# cwKeyer.net
KiCad netlist of a schematic drawn in EAGLE
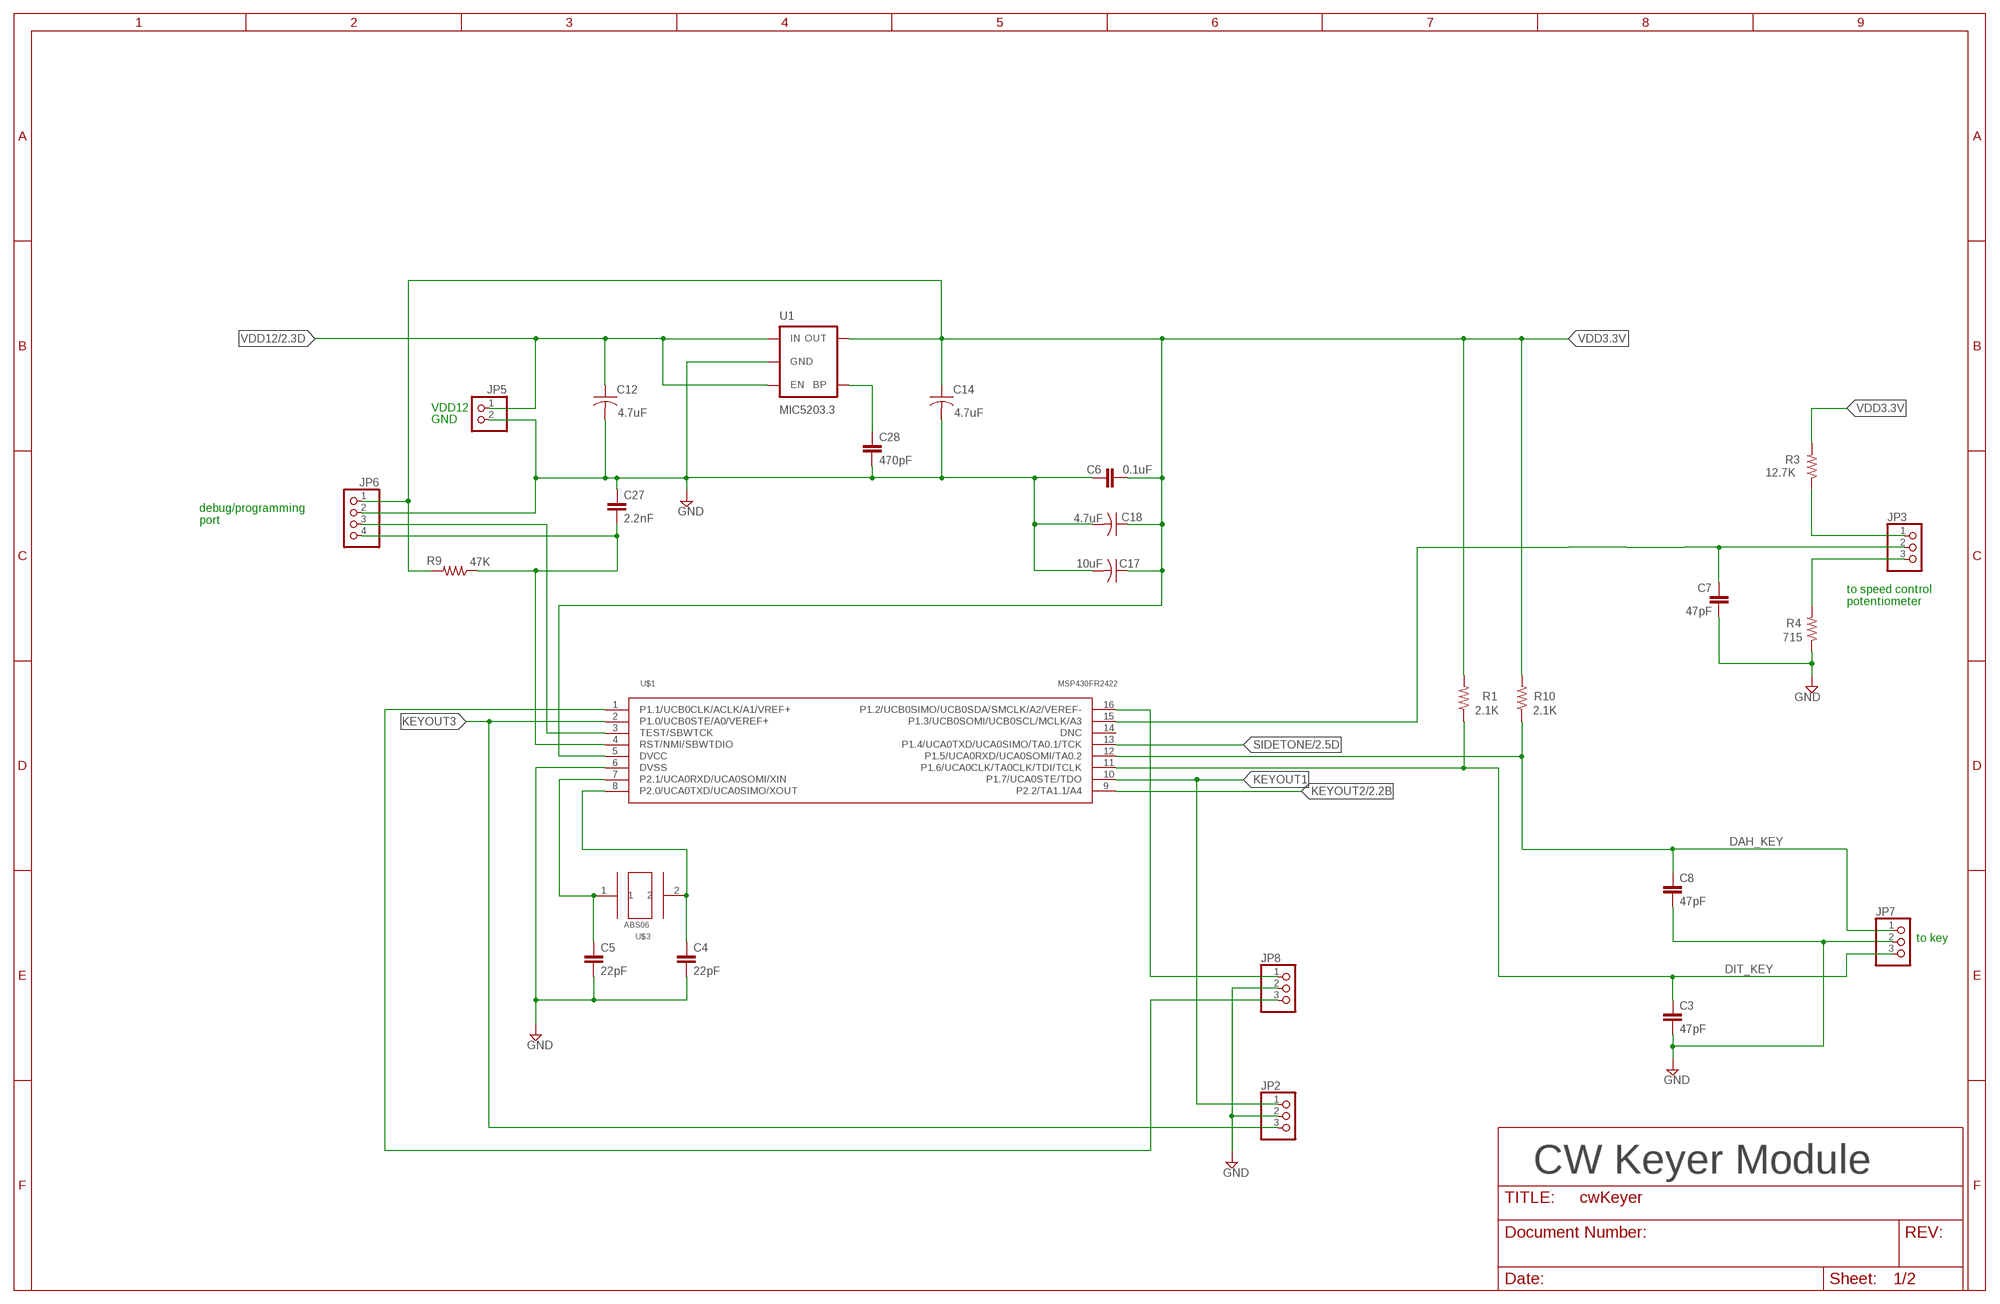
[diagram p0: schematic, sheet 1]
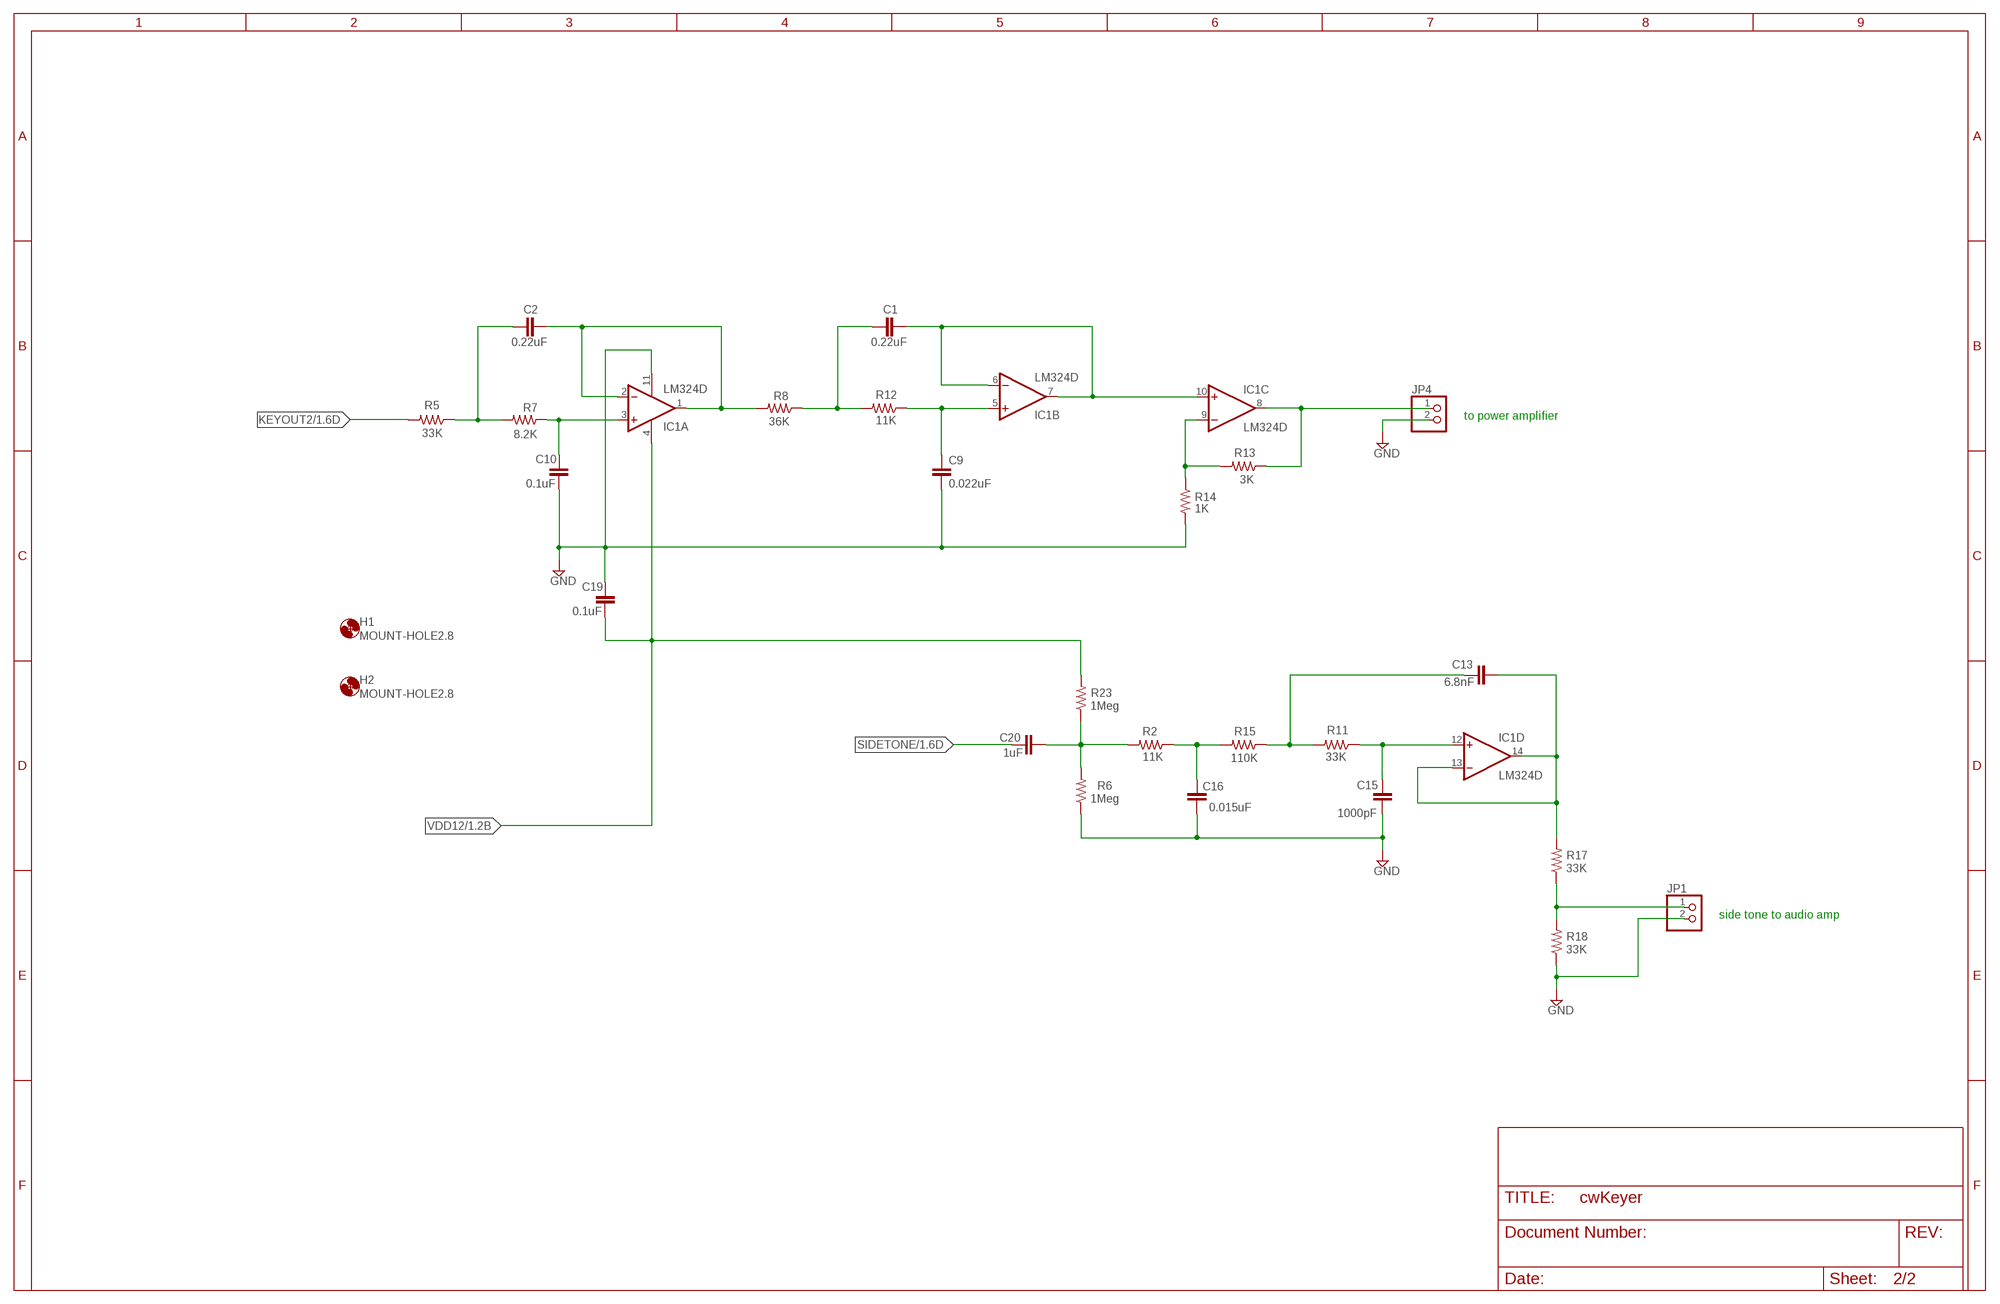
[diagram p1: schematic, sheet 2]

(export (version "E")
  (design (tool "Eeschema 10.0.6"))
  (components
    (comp (ref "C1")
      (value "0.22uF")
      (footprint "eagle-import:0603-CAP")
      (libsource (lib "eagle-import") (part "SparkFun-Passives_CAP0603-CAP"))
    )
    (comp (ref "C2")
      (value "0.22uF")
      (footprint "eagle-import:0603-CAP")
      (libsource (lib "eagle-import") (part "SparkFun-Passives_CAP0603-CAP"))
    )
    (comp (ref "C9")
      (value "0.022uF")
      (footprint "eagle-import:0603-CAP")
      (libsource (lib "eagle-import") (part "SparkFun-Passives_CAP0603-CAP"))
    )
    (comp (ref "C10")
      (value "0.1uF")
      (footprint "eagle-import:0603-CAP")
      (libsource (lib "eagle-import") (part "SparkFun-Passives_CAP0603-CAP"))
    )
    (comp (ref "C13")
      (value "6.8nF")
      (footprint "eagle-import:0603-CAP")
      (libsource (lib "eagle-import") (part "SparkFun-Passives_CAP0603-CAP"))
    )
    (comp (ref "C15")
      (value "1000pF")
      (footprint "eagle-import:0603-CAP")
      (libsource (lib "eagle-import") (part "SparkFun-Passives_CAP0603-CAP"))
    )
    (comp (ref "C16")
      (value "0.015uF")
      (footprint "eagle-import:0603-CAP")
      (libsource (lib "eagle-import") (part "SparkFun-Passives_CAP0603-CAP"))
    )
    (comp (ref "C19")
      (value "0.1uF")
      (footprint "eagle-import:0603-CAP")
      (libsource (lib "eagle-import") (part "SparkFun-Passives_CAP0603-CAP"))
    )
    (comp (ref "C20")
      (value "1uF")
      (footprint "eagle-import:0603-CAP")
      (libsource (lib "eagle-import") (part "SparkFun-Passives_CAP0603-CAP"))
    )
    (comp (ref "H1")
      (value "MOUNT-HOLE2.8")
      (footprint "eagle-import:2,8")
      (libsource (lib "eagle-import") (part "MOUNT-HOLE2.8"))
    )
    (comp (ref "H2")
      (value "MOUNT-HOLE2.8")
      (footprint "eagle-import:2,8")
      (libsource (lib "eagle-import") (part "MOUNT-HOLE2.8"))
    )
    (comp (ref "IC1")
      (value "LM324D")
      (footprint "eagle-import:SO14")
      (fields (field (name "VENDOR") "Mouser") (field (name "VENDOR_PN") "595-LM324DR"))
      (libsource (lib "eagle-import") (part "LM324D"))
    )
    (comp (ref "JP1")
      (value "PINHD-1X2")
      (footprint "eagle-import:1X02")
      (libsource (lib "eagle-import") (part "PINHD-1X2"))
    )
    (comp (ref "JP4")
      (value "PINHD-1X2")
      (footprint "eagle-import:1X02")
      (libsource (lib "eagle-import") (part "PINHD-1X2"))
    )
    (comp (ref "R2")
      (value "11K")
      (footprint "eagle-import:0603-RES")
      (libsource (lib "eagle-import") (part "RESISTOR0603-RES"))
    )
    (comp (ref "R5")
      (value "33K")
      (footprint "eagle-import:0603-RES")
      (libsource (lib "eagle-import") (part "RESISTOR0603-RES"))
    )
    (comp (ref "R6")
      (value "1Meg")
      (footprint "eagle-import:0603-RES")
      (libsource (lib "eagle-import") (part "RESISTOR0603-RES"))
    )
    (comp (ref "R7")
      (value "8.2K")
      (footprint "eagle-import:0603-RES")
      (libsource (lib "eagle-import") (part "RESISTOR0603-RES"))
    )
    (comp (ref "R8")
      (value "36K")
      (footprint "eagle-import:0603-RES")
      (libsource (lib "eagle-import") (part "RESISTOR0603-RES"))
    )
    (comp (ref "R11")
      (value "33K")
      (footprint "eagle-import:0603-RES")
      (libsource (lib "eagle-import") (part "RESISTOR0603-RES"))
    )
    (comp (ref "R12")
      (value "11K")
      (footprint "eagle-import:0603-RES")
      (libsource (lib "eagle-import") (part "RESISTOR0603-RES"))
    )
    (comp (ref "R13")
      (value "3K")
      (footprint "eagle-import:0603-RES")
      (libsource (lib "eagle-import") (part "RESISTOR0603-RES"))
    )
    (comp (ref "R14")
      (value "1K")
      (footprint "eagle-import:0603-RES")
      (libsource (lib "eagle-import") (part "RESISTOR0603-RES"))
    )
    (comp (ref "R15")
      (value "110K")
      (footprint "eagle-import:0603-RES")
      (libsource (lib "eagle-import") (part "RESISTOR0603-RES"))
    )
    (comp (ref "R17")
      (value "33K")
      (footprint "eagle-import:0603-RES")
      (libsource (lib "eagle-import") (part "RESISTOR0603-RES"))
    )
    (comp (ref "R18")
      (value "33K")
      (footprint "eagle-import:0603-RES")
      (libsource (lib "eagle-import") (part "RESISTOR0603-RES"))
    )
    (comp (ref "R23")
      (value "1Meg")
      (footprint "eagle-import:0603-RES")
      (libsource (lib "eagle-import") (part "RESISTOR0603-RES"))
    )
    (comp (ref "C3")
      (value "47pF")
      (footprint "eagle-import:0603-CAP")
      (libsource (lib "eagle-import") (part "SparkFun-Passives_CAP0603-CAP"))
    )
    (comp (ref "C4")
      (value "22pF")
      (footprint "eagle-import:0603-CAP")
      (libsource (lib "eagle-import") (part "CAP0603-CAP"))
    )
    (comp (ref "C5")
      (value "22pF")
      (footprint "eagle-import:0603-CAP")
      (libsource (lib "eagle-import") (part "CAP0603-CAP"))
    )
    (comp (ref "C6")
      (value "0.1uF")
      (footprint "eagle-import:0603-CAP")
      (libsource (lib "eagle-import") (part "SparkFun-Passives_CAP0603-CAP"))
    )
    (comp (ref "C7")
      (value "47pF")
      (footprint "eagle-import:0603-CAP")
      (libsource (lib "eagle-import") (part "SparkFun-Passives_CAP0603-CAP"))
    )
    (comp (ref "C8")
      (value "47pF")
      (footprint "eagle-import:0603-CAP")
      (libsource (lib "eagle-import") (part "SparkFun-Passives_CAP0603-CAP"))
    )
    (comp (ref "C12")
      (value "4.7uF")
      (footprint "eagle-import:C0603")
      (libsource (lib "eagle-import") (part "C-USC0603"))
    )
    (comp (ref "C14")
      (value "4.7uF")
      (footprint "eagle-import:C0603")
      (libsource (lib "eagle-import") (part "C-USC0603"))
    )
    (comp (ref "C17")
      (value "10uF")
      (footprint "eagle-import:C0805")
      (libsource (lib "eagle-import") (part "C-USC0805"))
    )
    (comp (ref "C18")
      (value "4.7uF")
      (footprint "eagle-import:C0603")
      (libsource (lib "eagle-import") (part "C-USC0603"))
    )
    (comp (ref "C27")
      (value "2.2nF")
      (footprint "eagle-import:0603-CAP")
      (libsource (lib "eagle-import") (part "SparkFun-Passives_CAP0603-CAP"))
    )
    (comp (ref "C28")
      (value "470pF")
      (footprint "eagle-import:0603-CAP")
      (libsource (lib "eagle-import") (part "CAP0603-CAP"))
    )
    (comp (ref "JP2")
      (value "PINHD-1X3")
      (footprint "eagle-import:1X03")
      (libsource (lib "eagle-import") (part "PINHD-1X3"))
    )
    (comp (ref "JP3")
      (value "PINHD-1X3")
      (footprint "eagle-import:1X03")
      (libsource (lib "eagle-import") (part "PINHD-1X3"))
    )
    (comp (ref "JP5")
      (value "PINHD-1X2")
      (footprint "eagle-import:1X02")
      (libsource (lib "eagle-import") (part "PINHD-1X2"))
    )
    (comp (ref "JP6")
      (value "PINHD-1X4")
      (footprint "eagle-import:1X04")
      (libsource (lib "eagle-import") (part "PINHD-1X4"))
    )
    (comp (ref "JP7")
      (value "PINHD-1X3")
      (footprint "eagle-import:1X03")
      (libsource (lib "eagle-import") (part "PINHD-1X3"))
    )
    (comp (ref "JP8")
      (value "PINHD-1X3")
      (footprint "eagle-import:1X03")
      (libsource (lib "eagle-import") (part "PINHD-1X3"))
    )
    (comp (ref "R1")
      (value "2.1K")
      (footprint "eagle-import:0603-RES")
      (libsource (lib "eagle-import") (part "RESISTOR0603-RES"))
    )
    (comp (ref "R3")
      (value "12.7K")
      (footprint "eagle-import:0603-RES")
      (libsource (lib "eagle-import") (part "RESISTOR0603-RES"))
    )
    (comp (ref "R4")
      (value "715")
      (footprint "eagle-import:0603-RES")
      (libsource (lib "eagle-import") (part "RESISTOR0603-RES"))
    )
    (comp (ref "R9")
      (value "47K")
      (footprint "eagle-import:0603-RES")
      (libsource (lib "eagle-import") (part "RESISTOR0603-RES"))
    )
    (comp (ref "R10")
      (value "2.1K")
      (footprint "eagle-import:0603-RES")
      (libsource (lib "eagle-import") (part "RESISTOR0603-RES"))
    )
    (comp (ref "U$1")
      (value "MSP430FR2422")
      (footprint "eagle-import:TSSOP16")
      (libsource (lib "eagle-import") (part "MSP430FR2422"))
    )
    (comp (ref "U$3")
      (value "ABS06")
      (footprint "eagle-import:ABS06")
      (libsource (lib "eagle-import") (part "ABS06"))
    )
    (comp (ref "U1")
      (value "MIC5203.3")
      (footprint "eagle-import:SOT23-5")
      (libsource (lib "eagle-import") (part "MIC52053.3V"))
    )
  )
  (nets
    (net (code "1") (name "DAH_KEY") (class "Default")
      (node (ref "C8") (pin "1") (pinfunction "1_1") (pintype "passive"))
      (node (ref "JP7") (pin "1") (pinfunction "1_1") (pintype "passive"))
      (node (ref "R10") (pin "1") (pinfunction "1_1") (pintype "passive"))
      (node (ref "U$1") (pin "12") (pinfunction "P1.5/UCA0RXD/UCA0SOMI/TA0.2_12") (pintype "bidirectional"))
    )
    (net (code "2") (name "DIT_KEY") (class "Default")
      (node (ref "C3") (pin "1") (pinfunction "1_1") (pintype "passive"))
      (node (ref "JP7") (pin "3") (pinfunction "3_3") (pintype "passive"))
      (node (ref "R1") (pin "1") (pinfunction "1_1") (pintype "passive"))
      (node (ref "U$1") (pin "11") (pinfunction "P1.6/UCA0CLK/TA0CLK/TDI/TCLK_11") (pintype "bidirectional"))
    )
    (net (code "3") (name "GND") (class "Default")
      (node (ref "C10") (pin "2") (pinfunction "2_2") (pintype "passive"))
      (node (ref "C12") (pin "2") (pinfunction "2_2") (pintype "passive"))
      (node (ref "C14") (pin "2") (pinfunction "2_2") (pintype "passive"))
      (node (ref "C15") (pin "1") (pinfunction "1_1") (pintype "passive"))
      (node (ref "C16") (pin "1") (pinfunction "1_1") (pintype "passive"))
      (node (ref "C17") (pin "2") (pinfunction "2_2") (pintype "passive"))
      (node (ref "C18") (pin "2") (pinfunction "2_2") (pintype "passive"))
      (node (ref "C19") (pin "1") (pinfunction "1_1") (pintype "passive"))
      (node (ref "C27") (pin "1") (pinfunction "1_1") (pintype "passive"))
      (node (ref "C28") (pin "2") (pinfunction "2_2") (pintype "passive"))
      (node (ref "C3") (pin "2") (pinfunction "2_2") (pintype "passive"))
      (node (ref "C4") (pin "2") (pinfunction "2_2") (pintype "passive"))
      (node (ref "C5") (pin "2") (pinfunction "2_2") (pintype "passive"))
      (node (ref "C6") (pin "2") (pinfunction "2_2") (pintype "passive"))
      (node (ref "C7") (pin "2") (pinfunction "2_2") (pintype "passive"))
      (node (ref "C8") (pin "2") (pinfunction "2_2") (pintype "passive"))
      (node (ref "C9") (pin "2") (pinfunction "2_2") (pintype "passive"))
      (node (ref "IC1") (pin "11") (pinfunction "V-_11") (pintype "power_in"))
      (node (ref "JP1") (pin "2") (pinfunction "2_2") (pintype "passive"))
      (node (ref "JP2") (pin "2") (pinfunction "2_2") (pintype "passive"))
      (node (ref "JP4") (pin "2") (pinfunction "2_2") (pintype "passive"))
      (node (ref "JP5") (pin "2") (pinfunction "2_2") (pintype "passive"))
      (node (ref "JP6") (pin "2") (pinfunction "2_2") (pintype "passive"))
      (node (ref "JP7") (pin "2") (pinfunction "2_2") (pintype "passive"))
      (node (ref "JP8") (pin "2") (pinfunction "2_2") (pintype "passive"))
      (node (ref "R14") (pin "2") (pinfunction "2_2") (pintype "passive"))
      (node (ref "R18") (pin "1") (pinfunction "1_1") (pintype "passive"))
      (node (ref "R4") (pin "1") (pinfunction "1_1") (pintype "passive"))
      (node (ref "R6") (pin "1") (pinfunction "1_1") (pintype "passive"))
      (node (ref "U$1") (pin "6") (pinfunction "DVSS_6") (pintype "bidirectional"))
      (node (ref "U1") (pin "2") (pinfunction "GND_2") (pintype "input"))
    )
    (net (code "4") (name "KEYOUT1") (class "Default")
      (node (ref "JP2") (pin "1") (pinfunction "1_1") (pintype "passive"))
      (node (ref "U$1") (pin "10") (pinfunction "P1.7/UCA0STE/TDO_10") (pintype "bidirectional"))
    )
    (net (code "5") (name "KEYOUT2") (class "Default")
      (node (ref "R5") (pin "2") (pinfunction "2_2") (pintype "passive"))
      (node (ref "U$1") (pin "9") (pinfunction "P2.2/TA1.1/A4_9") (pintype "bidirectional"))
    )
    (net (code "6") (name "KEYOUT3") (class "Default")
      (node (ref "JP2") (pin "3") (pinfunction "3_3") (pintype "passive"))
      (node (ref "U$1") (pin "2") (pinfunction "P1.0/UCB0STE/A0/VEREF+_2") (pintype "bidirectional"))
    )
    (net (code "7") (name "Net-(C1-Pad1)") (class "Default")
      (node (ref "C1") (pin "1") (pinfunction "1_1") (pintype "passive"))
      (node (ref "R12") (pin "2") (pinfunction "2_2") (pintype "passive"))
      (node (ref "R8") (pin "1") (pinfunction "1_1") (pintype "passive"))
    )
    (net (code "8") (name "Net-(C2-Pad1)") (class "Default")
      (node (ref "C2") (pin "1") (pinfunction "1_1") (pintype "passive"))
      (node (ref "R5") (pin "1") (pinfunction "1_1") (pintype "passive"))
      (node (ref "R7") (pin "2") (pinfunction "2_2") (pintype "passive"))
    )
    (net (code "9") (name "Net-(C13-Pad1)") (class "Default")
      (node (ref "C13") (pin "1") (pinfunction "1_1") (pintype "passive"))
      (node (ref "R11") (pin "2") (pinfunction "2_2") (pintype "passive"))
      (node (ref "R15") (pin "1") (pinfunction "1_1") (pintype "passive"))
    )
    (net (code "10") (name "Net-(C16-Pad2)") (class "Default")
      (node (ref "C16") (pin "2") (pinfunction "2_2") (pintype "passive"))
      (node (ref "R15") (pin "2") (pinfunction "2_2") (pintype "passive"))
      (node (ref "R2") (pin "1") (pinfunction "1_1") (pintype "passive"))
    )
    (net (code "11") (name "Net-(C20-Pad2)") (class "Default")
      (node (ref "C20") (pin "2") (pinfunction "2_2") (pintype "passive"))
      (node (ref "R2") (pin "2") (pinfunction "2_2") (pintype "passive"))
      (node (ref "R23") (pin "1") (pinfunction "1_1") (pintype "passive"))
      (node (ref "R6") (pin "2") (pinfunction "2_2") (pintype "passive"))
    )
    (net (code "12") (name "Net-(IC1A-+IN)") (class "Default")
      (node (ref "C10") (pin "1") (pinfunction "1_1") (pintype "passive"))
      (node (ref "IC1") (pin "3") (pinfunction "+IN_3") (pintype "input"))
      (node (ref "R7") (pin "1") (pinfunction "1_1") (pintype "passive"))
    )
    (net (code "13") (name "Net-(IC1A--IN)") (class "Default")
      (node (ref "C2") (pin "2") (pinfunction "2_2") (pintype "passive"))
      (node (ref "IC1") (pin "1") (pinfunction "OUT_1") (pintype "output"))
      (node (ref "IC1") (pin "2") (pinfunction "-IN_2") (pintype "input"))
      (node (ref "R8") (pin "2") (pinfunction "2_2") (pintype "passive"))
    )
    (net (code "14") (name "Net-(IC1B-+IN)") (class "Default")
      (node (ref "C9") (pin "1") (pinfunction "1_1") (pintype "passive"))
      (node (ref "IC1") (pin "5") (pinfunction "+IN_5") (pintype "input"))
      (node (ref "R12") (pin "1") (pinfunction "1_1") (pintype "passive"))
    )
    (net (code "15") (name "Net-(IC1B--IN)") (class "Default")
      (node (ref "C1") (pin "2") (pinfunction "2_2") (pintype "passive"))
      (node (ref "IC1") (pin "10") (pinfunction "+IN_10") (pintype "input"))
      (node (ref "IC1") (pin "6") (pinfunction "-IN_6") (pintype "input"))
      (node (ref "IC1") (pin "7") (pinfunction "OUT_7") (pintype "output"))
    )
    (net (code "16") (name "Net-(IC1C--IN)") (class "Default")
      (node (ref "IC1") (pin "9") (pinfunction "-IN_9") (pintype "input"))
      (node (ref "R13") (pin "2") (pinfunction "2_2") (pintype "passive"))
      (node (ref "R14") (pin "1") (pinfunction "1_1") (pintype "passive"))
    )
    (net (code "17") (name "Net-(IC1C-OUT)") (class "Default")
      (node (ref "IC1") (pin "8") (pinfunction "OUT_8") (pintype "output"))
      (node (ref "JP4") (pin "1") (pinfunction "1_1") (pintype "passive"))
      (node (ref "R13") (pin "1") (pinfunction "1_1") (pintype "passive"))
    )
    (net (code "18") (name "Net-(IC1D-+IN)") (class "Default")
      (node (ref "C15") (pin "2") (pinfunction "2_2") (pintype "passive"))
      (node (ref "IC1") (pin "12") (pinfunction "+IN_12") (pintype "input"))
      (node (ref "R11") (pin "1") (pinfunction "1_1") (pintype "passive"))
    )
    (net (code "19") (name "Net-(IC1D--IN)") (class "Default")
      (node (ref "C13") (pin "2") (pinfunction "2_2") (pintype "passive"))
      (node (ref "IC1") (pin "13") (pinfunction "-IN_13") (pintype "input"))
      (node (ref "IC1") (pin "14") (pinfunction "OUT_14") (pintype "output"))
      (node (ref "R17") (pin "2") (pinfunction "2_2") (pintype "passive"))
    )
    (net (code "20") (name "Net-(JP1-Pad1)") (class "Default")
      (node (ref "JP1") (pin "1") (pinfunction "1_1") (pintype "passive"))
      (node (ref "R17") (pin "1") (pinfunction "1_1") (pintype "passive"))
      (node (ref "R18") (pin "2") (pinfunction "2_2") (pintype "passive"))
    )
    (net (code "21") (name "Net-(JP3-Pad1)") (class "Default")
      (node (ref "JP3") (pin "1") (pinfunction "1_1") (pintype "passive"))
      (node (ref "R3") (pin "1") (pinfunction "1_1") (pintype "passive"))
    )
    (net (code "22") (name "Net-(JP3-Pad3)") (class "Default")
      (node (ref "JP3") (pin "3") (pinfunction "3_3") (pintype "passive"))
      (node (ref "R4") (pin "2") (pinfunction "2_2") (pintype "passive"))
    )
    (net (code "23") (name "Net-(U$1-P1.1{slash}UCB0CLK{slash}ACLK{slash}A1{slash}VREF+)") (class "Default")
      (node (ref "JP8") (pin "3") (pinfunction "3_3") (pintype "passive"))
      (node (ref "U$1") (pin "1") (pinfunction "P1.1/UCB0CLK/ACLK/A1/VREF+_1") (pintype "bidirectional"))
    )
    (net (code "24") (name "Net-(U$1-P1.2{slash}UCB0SIMO{slash}UCB0SDA{slash}SMCLK{slash}A2{slash}VEREF-)") (class "Default")
      (node (ref "JP8") (pin "1") (pinfunction "1_1") (pintype "passive"))
      (node (ref "U$1") (pin "16") (pinfunction "P1.2/UCB0SIMO/UCB0SDA/SMCLK/A2/VEREF-_16") (pintype "bidirectional"))
    )
    (net (code "25") (name "Net-(U$1-P1.3{slash}UCB0SOMI{slash}UCB0SCL{slash}MCLK{slash}A3)") (class "Default")
      (node (ref "C7") (pin "1") (pinfunction "1_1") (pintype "passive"))
      (node (ref "JP3") (pin "2") (pinfunction "2_2") (pintype "passive"))
      (node (ref "U$1") (pin "15") (pinfunction "P1.3/UCB0SOMI/UCB0SCL/MCLK/A3_15") (pintype "bidirectional"))
    )
    (net (code "26") (name "Net-(U$1-P2.0{slash}UCA0TXD{slash}UCA0SIMO{slash}XOUT)") (class "Default")
      (node (ref "C4") (pin "1") (pinfunction "1_1") (pintype "passive"))
      (node (ref "U$1") (pin "8") (pinfunction "P2.0/UCA0TXD/UCA0SIMO/XOUT_8") (pintype "bidirectional"))
      (node (ref "U$3") (pin "2") (pinfunction "2_2") (pintype "bidirectional"))
    )
    (net (code "27") (name "Net-(U$1-P2.1{slash}UCA0RXD{slash}UCA0SOMI{slash}XIN)") (class "Default")
      (node (ref "C5") (pin "1") (pinfunction "1_1") (pintype "passive"))
      (node (ref "U$1") (pin "7") (pinfunction "P2.1/UCA0RXD/UCA0SOMI/XIN_7") (pintype "bidirectional"))
      (node (ref "U$3") (pin "1") (pinfunction "1_1") (pintype "bidirectional"))
    )
    (net (code "28") (name "Net-(U$1-RST{slash}NMI{slash}SBWTDIO)") (class "Default")
      (node (ref "C27") (pin "2") (pinfunction "2_2") (pintype "passive"))
      (node (ref "JP6") (pin "4") (pinfunction "4_4") (pintype "passive"))
      (node (ref "R9") (pin "1") (pinfunction "1_1") (pintype "passive"))
      (node (ref "U$1") (pin "4") (pinfunction "RST/NMI/SBWTDIO_4") (pintype "bidirectional"))
    )
    (net (code "29") (name "Net-(U$1-TEST{slash}SBWTCK)") (class "Default")
      (node (ref "JP6") (pin "3") (pinfunction "3_3") (pintype "passive"))
      (node (ref "U$1") (pin "3") (pinfunction "TEST/SBWTCK_3") (pintype "bidirectional"))
    )
    (net (code "30") (name "Net-(U1-BP)") (class "Default")
      (node (ref "C28") (pin "1") (pinfunction "1_1") (pintype "passive"))
      (node (ref "U1") (pin "4") (pinfunction "BP_4") (pintype "input"))
    )
    (net (code "31") (name "SIDETONE") (class "Default")
      (node (ref "C20") (pin "1") (pinfunction "1_1") (pintype "passive"))
      (node (ref "U$1") (pin "13") (pinfunction "P1.4/UCA0TXD/UCA0SIMO/TA0.1/TCK_13") (pintype "bidirectional"))
    )
    (net (code "32") (name "VDD3.3V") (class "Default")
      (node (ref "C14") (pin "1") (pinfunction "1_1") (pintype "passive"))
      (node (ref "C17") (pin "1") (pinfunction "1_1") (pintype "passive"))
      (node (ref "C18") (pin "1") (pinfunction "1_1") (pintype "passive"))
      (node (ref "C6") (pin "1") (pinfunction "1_1") (pintype "passive"))
      (node (ref "JP6") (pin "1") (pinfunction "1_1") (pintype "passive"))
      (node (ref "R1") (pin "2") (pinfunction "2_2") (pintype "passive"))
      (node (ref "R10") (pin "2") (pinfunction "2_2") (pintype "passive"))
      (node (ref "R3") (pin "2") (pinfunction "2_2") (pintype "passive"))
      (node (ref "R9") (pin "2") (pinfunction "2_2") (pintype "passive"))
      (node (ref "U$1") (pin "5") (pinfunction "DVCC_5") (pintype "bidirectional"))
      (node (ref "U1") (pin "5") (pinfunction "OUT_5") (pintype "passive"))
    )
    (net (code "33") (name "VDD12") (class "Default")
      (node (ref "C12") (pin "1") (pinfunction "1_1") (pintype "passive"))
      (node (ref "C19") (pin "2") (pinfunction "2_2") (pintype "passive"))
      (node (ref "IC1") (pin "4") (pinfunction "V+_4") (pintype "power_in"))
      (node (ref "JP5") (pin "1") (pinfunction "1_1") (pintype "passive"))
      (node (ref "R23") (pin "2") (pinfunction "2_2") (pintype "passive"))
      (node (ref "U1") (pin "1") (pinfunction "IN_1") (pintype "input"))
      (node (ref "U1") (pin "3") (pinfunction "EN_3") (pintype "input"))
    )
    (net (code "34") (name "unconnected-(U$1-DNC-Pad14)") (class "Default")
      (node (ref "U$1") (pin "14") (pinfunction "DNC_14") (pintype "bidirectional"))
    )
  )
)
